# momentary_2_way_switch.net
KiCad netlist of a schematic drawn in EAGLE
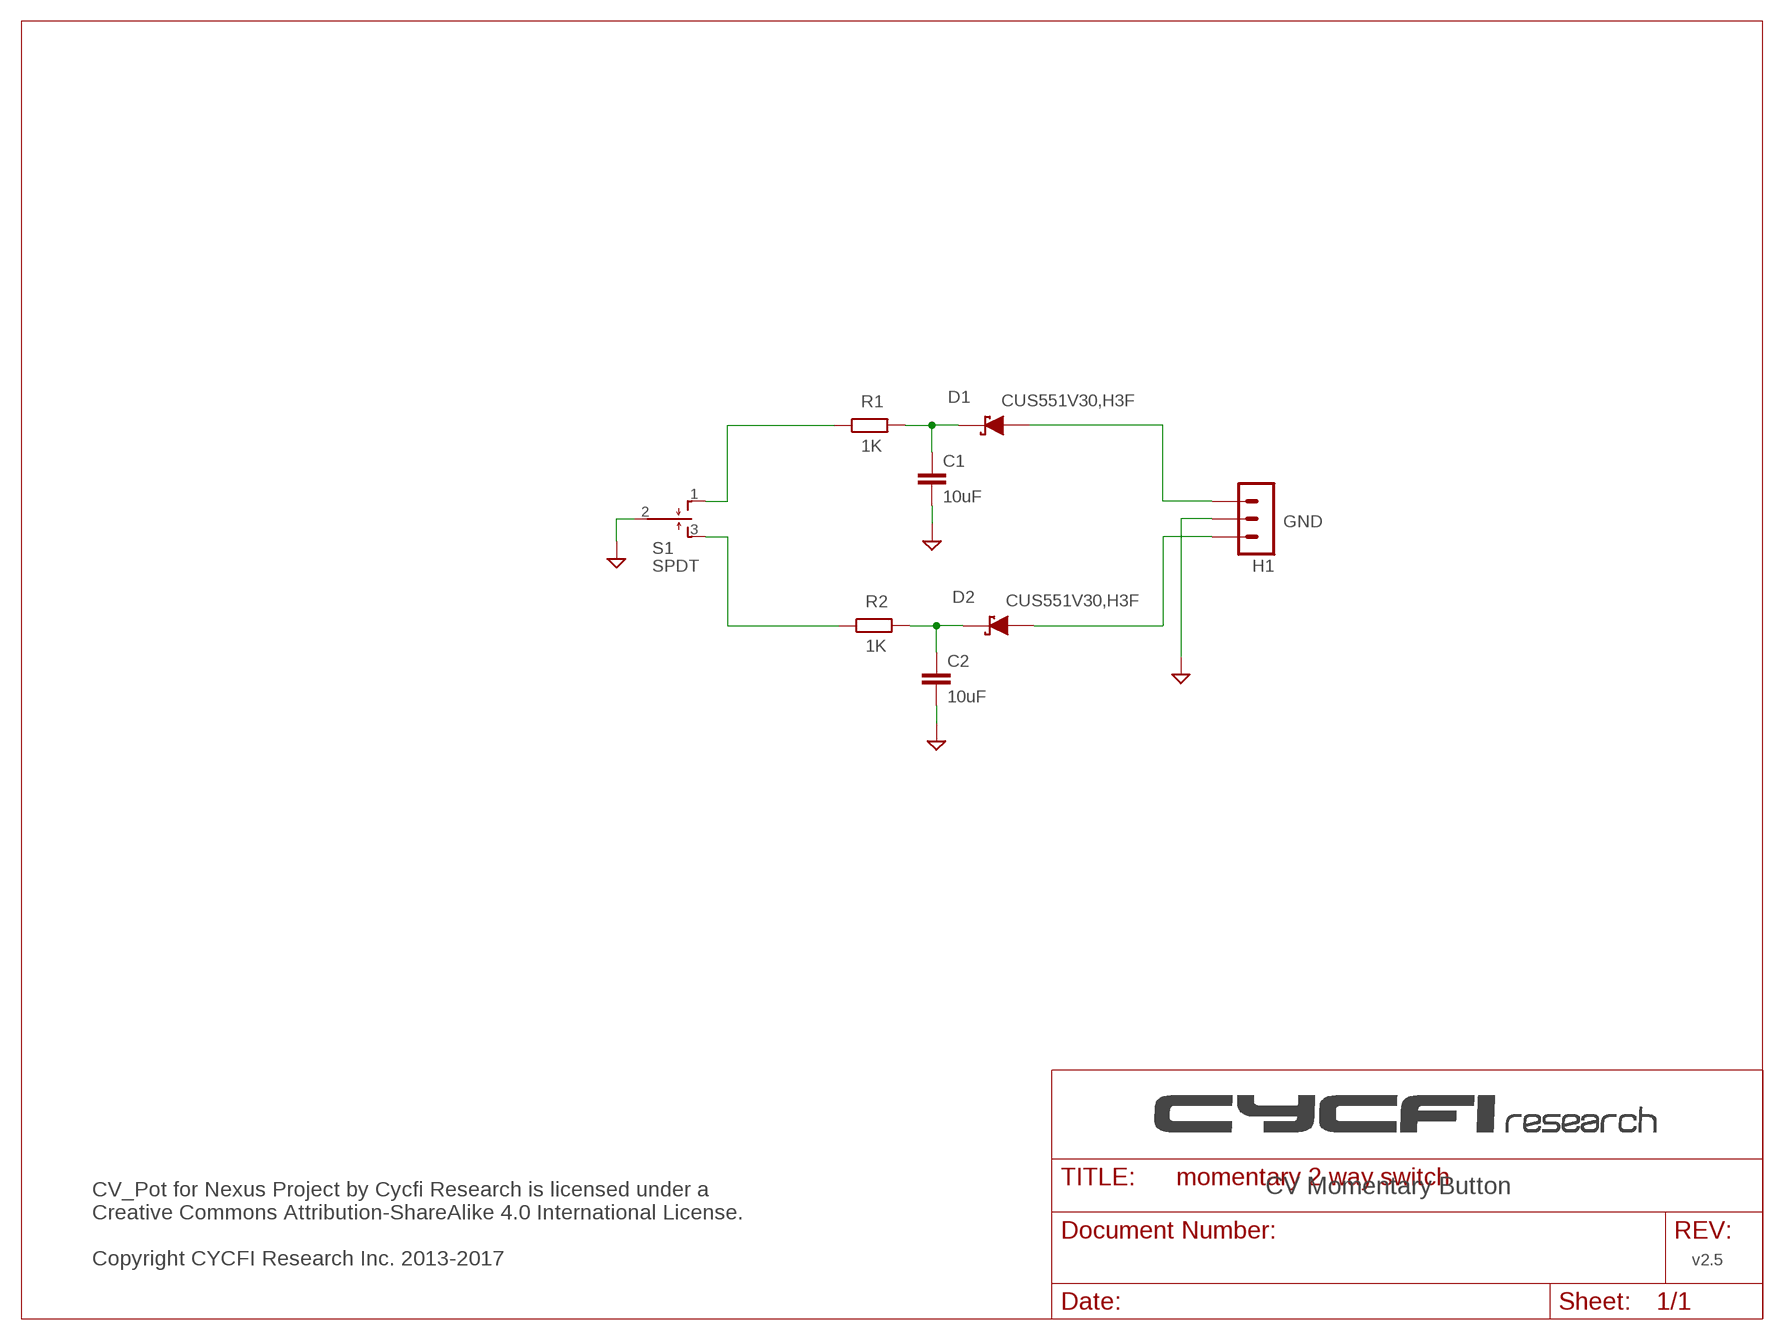
[diagram p0: schematic, sheet 1]

(export (version "E")
  (design (tool "Eeschema 10.0.6"))
  (components
    (comp (ref "C1")
      (value "10uF")
      (footprint "eagle-import:C0603")
      (libsource (lib "eagle-import") (part "C-EUC0603"))
    )
    (comp (ref "C2")
      (value "10uF")
      (footprint "eagle-import:C0603")
      (libsource (lib "eagle-import") (part "C-EUC0603"))
    )
    (comp (ref "D1")
      (value "CUS551V30,H3F")
      (footprint "eagle-import:SOD-323")
      (libsource (lib "eagle-import") (part "D_SCHOTTKYL"))
    )
    (comp (ref "D2")
      (value "CUS551V30,H3F")
      (footprint "eagle-import:SOD-323")
      (libsource (lib "eagle-import") (part "D_SCHOTTKYL"))
    )
    (comp (ref "H1")
      (value "3PIN-SMD-2.54MM")
      (footprint "eagle-import:3P-SMD-2.54MM")
      (libsource (lib "eagle-import") (part "3PIN-SMD-2.54MM"))
    )
    (comp (ref "R1")
      (value "1K")
      (footprint "eagle-import:R0402")
      (libsource (lib "eagle-import") (part "R-EU_R0402"))
    )
    (comp (ref "R2")
      (value "1K")
      (footprint "eagle-import:R0402")
      (libsource (lib "eagle-import") (part "R-EU_R0402"))
    )
    (comp (ref "S1")
      (value "SPDT")
      (footprint "eagle-import:SPDT")
      (libsource (lib "eagle-import") (part "SPDT"))
    )
  )
  (nets
    (net (code "1") (name "GND") (class "Default")
      (node (ref "C1") (pin "2") (pinfunction "2_2") (pintype "passive"))
      (node (ref "C2") (pin "2") (pinfunction "2_2") (pintype "passive"))
      (node (ref "H1") (pin "P$2") (pinfunction "2_P$2") (pintype "passive"))
      (node (ref "S1") (pin "2") (pinfunction "P_2") (pintype "passive"))
    )
    (net (code "2") (name "Net-(D1-A)") (class "Default")
      (node (ref "D1") (pin "1") (pinfunction "A_1") (pintype "passive"))
      (node (ref "H1") (pin "P$1") (pinfunction "1_P$1") (pintype "passive"))
    )
    (net (code "3") (name "Net-(D1-C)") (class "Default")
      (node (ref "C1") (pin "1") (pinfunction "1_1") (pintype "passive"))
      (node (ref "D1") (pin "2") (pinfunction "C_2") (pintype "passive"))
      (node (ref "R1") (pin "2") (pinfunction "2_2") (pintype "passive"))
    )
    (net (code "4") (name "Net-(D2-A)") (class "Default")
      (node (ref "D2") (pin "1") (pinfunction "A_1") (pintype "passive"))
      (node (ref "H1") (pin "P$3") (pinfunction "3_P$3") (pintype "passive"))
    )
    (net (code "5") (name "Net-(D2-C)") (class "Default")
      (node (ref "C2") (pin "1") (pinfunction "1_1") (pintype "passive"))
      (node (ref "D2") (pin "2") (pinfunction "C_2") (pintype "passive"))
      (node (ref "R2") (pin "2") (pinfunction "2_2") (pintype "passive"))
    )
    (net (code "6") (name "Net-(S1-O)") (class "Default")
      (node (ref "R1") (pin "1") (pinfunction "1_1") (pintype "passive"))
      (node (ref "S1") (pin "1") (pinfunction "O_1") (pintype "passive"))
    )
    (net (code "7") (name "Net-(S1-S)") (class "Default")
      (node (ref "R2") (pin "1") (pinfunction "1_1") (pintype "passive"))
      (node (ref "S1") (pin "3") (pinfunction "S_3") (pintype "passive"))
    )
  )
)
